# FanSCH.net
KiCad netlist of a schematic drawn in Altium Designer
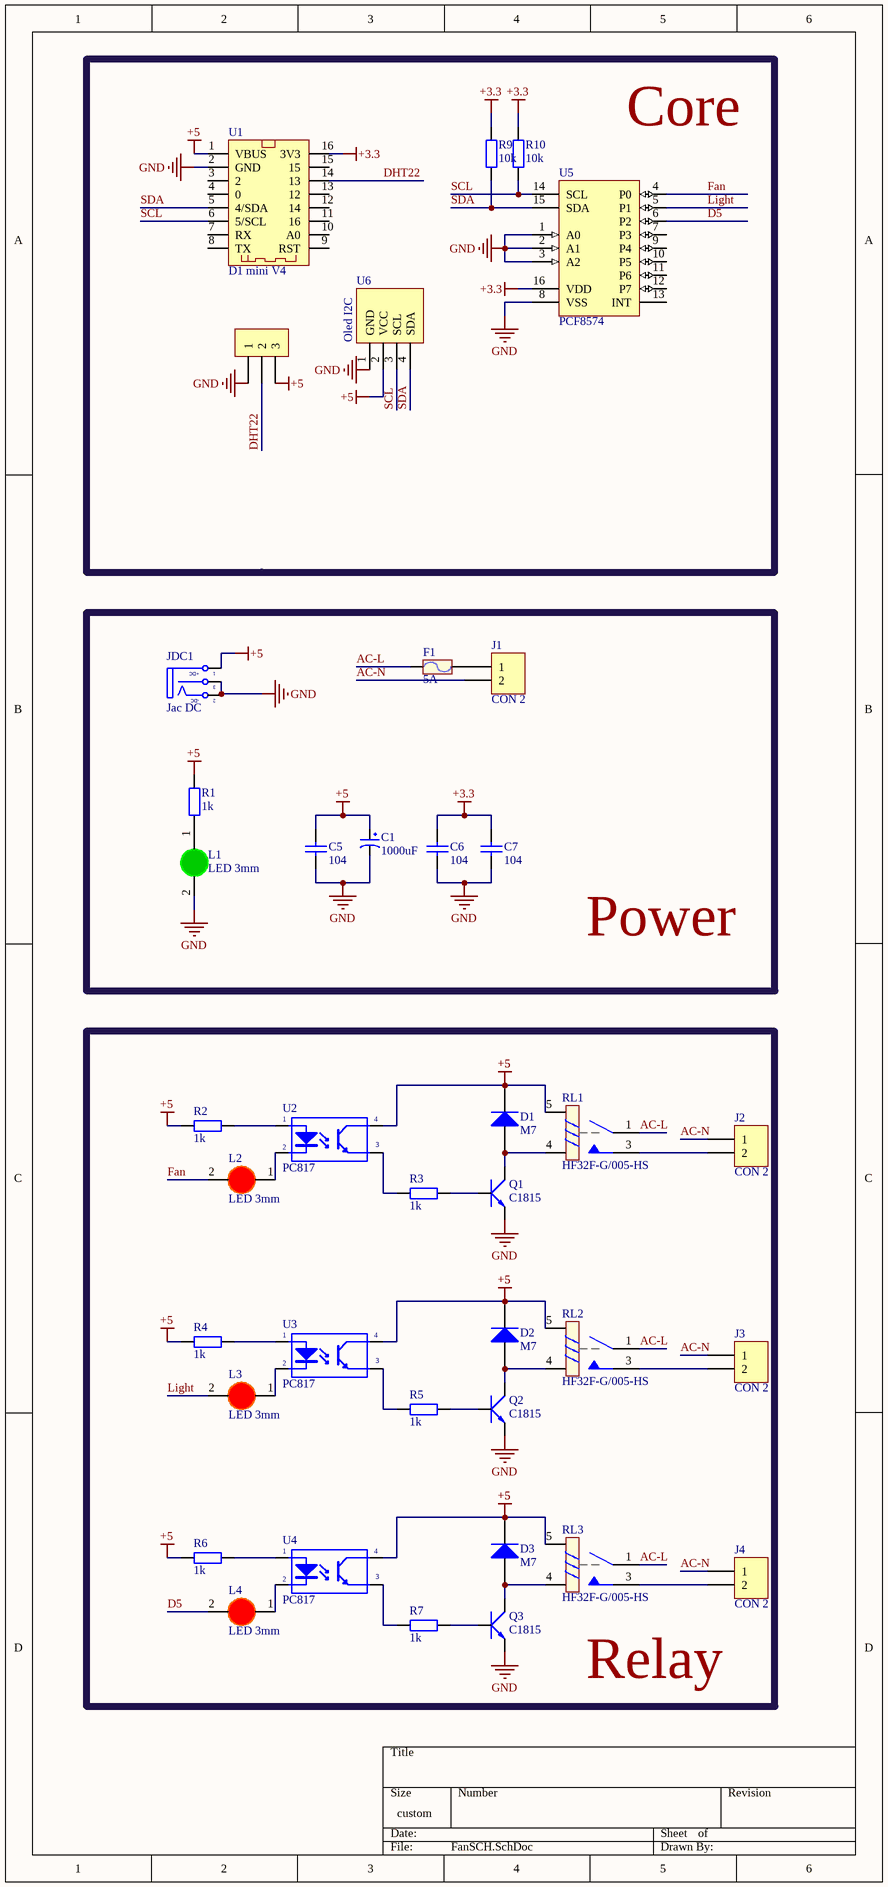
[diagram p0: FanSCH.SchDoc]

(export (version "E")
  (design (tool "Eeschema 10.0.6"))
  (components
    (comp (ref "C1")
      (value "1000uF")
      (footprint "tu hoa 8mm")
      (description "Cắm")
      (libsource (lib "Altium_Lib_by_KhueNguyenCreator") (part "Tu Hoa 1000uF 16V 8x20"))
    )
    (comp (ref "C5")
      (value "104")
      (footprint "tu 0603")
      (description "Dán")
      (libsource (lib "Altium_Lib_by_KhueNguyenCreator") (part "Tu 0603 104 50V 10%"))
    )
    (comp (ref "C6")
      (value "104")
      (footprint "tu 0603")
      (description "Dán")
      (libsource (lib "Altium_Lib_by_KhueNguyenCreator") (part "Tu 0603 104 50V 10%"))
    )
    (comp (ref "C7")
      (value "104")
      (footprint "tu 0603")
      (description "Dán")
      (libsource (lib "Altium_Lib_by_KhueNguyenCreator") (part "Tu 0603 104 50V 10%"))
    )
    (comp (ref "D1")
      (value "M7")
      (footprint "DIODE SMA")
      (description "Dán")
      (libsource (lib "Altium_Lib_by_KhueNguyenCreator") (part "Diode M7 ( 4007 )"))
    )
    (comp (ref "D2")
      (value "M7")
      (footprint "DIODE SMA")
      (description "Dán")
      (libsource (lib "Altium_Lib_by_KhueNguyenCreator") (part "Diode M7 ( 4007 )"))
    )
    (comp (ref "D3")
      (value "M7")
      (footprint "DIODE SMA")
      (description "Dán")
      (libsource (lib "Altium_Lib_by_KhueNguyenCreator") (part "Diode M7 ( 4007 )"))
    )
    (comp (ref "F1")
      (value "5A")
      (footprint "Fuse rectangular")
      (description "Fuse")
      (fields (field (name "DESIGNED BY") "VanDungEvn"))
      (libsource (lib "iuh-thuc-hanh") (part "Fuse"))
    )
    (comp (ref "H1")
      (value "Header 3P VH3.96 Duc Thang")
      (footprint "VH3.96M-3")
      (description "Cắm")
      (libsource (lib "Altium_Lib_by_KhueNguyenCreator") (part "Header 3P VH3.96 Duc Thang"))
    )
    (comp (ref "J1")
      (value "CON 2")
      (footprint "CON 2 2EDG5.08")
      (description "CON2 KF terminal")
      (libsource (lib "iuh-thuc-hanh") (part "CON 2 EDG5.08"))
    )
    (comp (ref "J2")
      (value "CON 2")
      (footprint "CON 2 2EDG5.08")
      (description "CON2 KF terminal")
      (libsource (lib "iuh-thuc-hanh") (part "CON 2 EDG5.08"))
    )
    (comp (ref "J3")
      (value "CON 2")
      (footprint "CON 2 2EDG5.08")
      (description "CON2 KF terminal")
      (libsource (lib "iuh-thuc-hanh") (part "CON 2 EDG5.08"))
    )
    (comp (ref "J4")
      (value "CON 2")
      (footprint "CON 2 2EDG5.08")
      (description "CON2 KF terminal")
      (libsource (lib "iuh-thuc-hanh") (part "CON 2 EDG5.08"))
    )
    (comp (ref "JDC1")
      (value "Jac DC")
      (footprint "DC0")
      (description "Jac DC input")
      (libsource (lib "LIBRARY1") (part "DCIN"))
    )
    (comp (ref "L1")
      (value "LED 3mm")
      (footprint "LED-3MM-GREEN")
      (description "Cắm")
      (libsource (lib "Altium_Lib_by_KhueNguyenCreator") (part "LED 3mm Xanh La"))
    )
    (comp (ref "L2")
      (value "LED 3mm")
      (footprint "LED-3MM-RED")
      (description "Cắm")
      (libsource (lib "Altium_Lib_by_KhueNguyenCreator") (part "LED 3mm Do"))
    )
    (comp (ref "L3")
      (value "LED 3mm")
      (footprint "LED-3MM-RED")
      (description "Cắm")
      (libsource (lib "Altium_Lib_by_KhueNguyenCreator") (part "LED 3mm Do"))
    )
    (comp (ref "L4")
      (value "LED 3mm")
      (footprint "LED-3MM-RED")
      (description "Cắm")
      (libsource (lib "Altium_Lib_by_KhueNguyenCreator") (part "LED 3mm Do"))
    )
    (comp (ref "Q1")
      (value "C1815")
      (footprint "TO92")
      (description "NPN transistor")
      (libsource (lib "Altium_Lib_by_KhueNguyenCreator") (part "Trans C1815 DIP"))
    )
    (comp (ref "Q2")
      (value "C1815")
      (footprint "TO92")
      (description "NPN transistor")
      (libsource (lib "Altium_Lib_by_KhueNguyenCreator") (part "Trans C1815 DIP"))
    )
    (comp (ref "Q3")
      (value "C1815")
      (footprint "TO92")
      (description "NPN transistor")
      (libsource (lib "Altium_Lib_by_KhueNguyenCreator") (part "Trans C1815 DIP"))
    )
    (comp (ref "R1")
      (value "1k")
      (footprint "tro smd 0603")
      (description "Dán")
      (libsource (lib "Altium_Lib_by_KhueNguyenCreator") (part "Tro 0603 1% 1k"))
    )
    (comp (ref "R2")
      (value "1k")
      (footprint "tro smd 0603")
      (description "Dán")
      (libsource (lib "Altium_Lib_by_KhueNguyenCreator") (part "Tro 0603 1% 1k"))
    )
    (comp (ref "R3")
      (value "1k")
      (footprint "tro smd 0603")
      (description "Dán")
      (libsource (lib "Altium_Lib_by_KhueNguyenCreator") (part "Tro 0603 1% 1k"))
    )
    (comp (ref "R4")
      (value "1k")
      (footprint "tro smd 0603")
      (description "Dán")
      (libsource (lib "Altium_Lib_by_KhueNguyenCreator") (part "Tro 0603 1% 1k"))
    )
    (comp (ref "R5")
      (value "1k")
      (footprint "tro smd 0603")
      (description "Dán")
      (libsource (lib "Altium_Lib_by_KhueNguyenCreator") (part "Tro 0603 1% 1k"))
    )
    (comp (ref "R6")
      (value "1k")
      (footprint "tro smd 0603")
      (description "Dán")
      (libsource (lib "Altium_Lib_by_KhueNguyenCreator") (part "Tro 0603 1% 1k"))
    )
    (comp (ref "R7")
      (value "1k")
      (footprint "tro smd 0603")
      (description "Dán")
      (libsource (lib "Altium_Lib_by_KhueNguyenCreator") (part "Tro 0603 1% 1k"))
    )
    (comp (ref "R9")
      (value "10k")
      (footprint "tro smd 0603")
      (description "Dán")
      (libsource (lib "Altium_Lib_by_KhueNguyenCreator") (part "Tro 0603 1% 10k"))
    )
    (comp (ref "R10")
      (value "10k")
      (footprint "tro smd 0603")
      (description "Dán")
      (libsource (lib "Altium_Lib_by_KhueNguyenCreator") (part "Tro 0603 1% 10k"))
    )
    (comp (ref "RL1")
      (value "HF32F-G/005-HS")
      (footprint "HF32F-G")
      (description "Relay hongfa 10A 4P HF32F-G/005-HS")
      (libsource (lib "iuh-thuc-hanh") (part "Relay HF 10A"))
    )
    (comp (ref "RL2")
      (value "HF32F-G/005-HS")
      (footprint "HF32F-G")
      (description "Relay hongfa 10A 4P HF32F-G/005-HS")
      (libsource (lib "iuh-thuc-hanh") (part "Relay HF 10A"))
    )
    (comp (ref "RL3")
      (value "HF32F-G/005-HS")
      (footprint "HF32F-G")
      (description "Relay hongfa 10A 4P HF32F-G/005-HS")
      (libsource (lib "iuh-thuc-hanh") (part "Relay HF 10A"))
    )
    (comp (ref "U1")
      (value "D1 mini V4")
      (footprint "WEMOS D1 MINI V4 USD")
      (description "ESP8266 D1")
      (libsource (lib "iuh-thuc-hanh") (part "Wemos D1 mini V4.0"))
    )
    (comp (ref "U2")
      (value "PC817")
      (footprint "DIP4")
      (description "Single Opto")
      (libsource (lib "LIBRARY1") (part "PC817"))
    )
    (comp (ref "U3")
      (value "PC817")
      (footprint "DIP4")
      (description "Single Opto")
      (libsource (lib "LIBRARY1") (part "PC817"))
    )
    (comp (ref "U4")
      (value "PC817")
      (footprint "DIP4")
      (description "Single Opto")
      (libsource (lib "LIBRARY1") (part "PC817"))
    )
    (comp (ref "U5") (value "PCF8574") (footprint "DIP16") (libsource (lib "iuh-thuc-hanh") (part "PCF8574")))
    (comp (ref "U6") (value "Oled I2C") (footprint "Oled") (libsource (lib "Nathzz") (part "Oled I2C")))
  )
  (nets
    (net (code "1") (name "+3.3") (class "Default")
      (node (ref "C6") (pin "2") (pinfunction "2_2") (pintype "passive"))
      (node (ref "C7") (pin "2") (pinfunction "2_2") (pintype "passive"))
      (node (ref "R10") (pin "2") (pinfunction "2_2") (pintype "passive"))
      (node (ref "R9") (pin "2") (pinfunction "2_2") (pintype "passive"))
      (node (ref "U1") (pin "16") (pinfunction "3V3_16") (pintype "passive"))
      (node (ref "U5") (pin "16") (pinfunction "VDD_16") (pintype "passive"))
    )
    (net (code "2") (name "+5") (class "Default")
      (node (ref "C1") (pin "1") (pinfunction "1_1") (pintype "passive"))
      (node (ref "C5") (pin "2") (pinfunction "2_2") (pintype "passive"))
      (node (ref "D1") (pin "2") (pinfunction "K_2") (pintype "passive"))
      (node (ref "D2") (pin "2") (pinfunction "K_2") (pintype "passive"))
      (node (ref "D3") (pin "2") (pinfunction "K_2") (pintype "passive"))
      (node (ref "H1") (pin "3") (pinfunction "3_3") (pintype "passive"))
      (node (ref "JDC1") (pin "1") (pinfunction "T_1") (pintype "passive"))
      (node (ref "R1") (pin "2") (pinfunction "2_2") (pintype "passive"))
      (node (ref "R2") (pin "1") (pinfunction "1_1") (pintype "passive"))
      (node (ref "R4") (pin "1") (pinfunction "1_1") (pintype "passive"))
      (node (ref "R6") (pin "1") (pinfunction "1_1") (pintype "passive"))
      (node (ref "RL1") (pin "5") (pinfunction "5_5") (pintype "passive"))
      (node (ref "RL2") (pin "5") (pinfunction "5_5") (pintype "passive"))
      (node (ref "RL3") (pin "5") (pinfunction "5_5") (pintype "passive"))
      (node (ref "U1") (pin "1") (pinfunction "VBUS_1") (pintype "passive"))
      (node (ref "U2") (pin "4") (pinfunction "C_4") (pintype "passive"))
      (node (ref "U3") (pin "4") (pinfunction "C_4") (pintype "passive"))
      (node (ref "U4") (pin "4") (pinfunction "C_4") (pintype "passive"))
      (node (ref "U6") (pin "2") (pinfunction "VCC_2") (pintype "passive"))
    )
    (net (code "3") (name "/AC-L") (class "Default")
      (node (ref "F1") (pin "1") (pinfunction "1_1") (pintype "passive"))
      (node (ref "RL1") (pin "1") (pinfunction "1_1") (pintype "passive"))
      (node (ref "RL2") (pin "1") (pinfunction "1_1") (pintype "passive"))
      (node (ref "RL3") (pin "1") (pinfunction "1_1") (pintype "passive"))
    )
    (net (code "4") (name "/AC-N") (class "Default")
      (node (ref "J1") (pin "2") (pinfunction "2_2") (pintype "passive"))
      (node (ref "J2") (pin "1") (pinfunction "1_1") (pintype "passive"))
      (node (ref "J3") (pin "1") (pinfunction "1_1") (pintype "passive"))
      (node (ref "J4") (pin "1") (pinfunction "1_1") (pintype "passive"))
    )
    (net (code "5") (name "/D5") (class "Default")
      (node (ref "L4") (pin "2") (pinfunction "K_2") (pintype "passive"))
      (node (ref "U5") (pin "6") (pinfunction "P2_6") (pintype "bidirectional"))
    )
    (net (code "6") (name "/DHT22") (class "Default")
      (node (ref "H1") (pin "2") (pinfunction "2_2") (pintype "passive"))
      (node (ref "U1") (pin "14") (pinfunction "13_14") (pintype "passive"))
    )
    (net (code "7") (name "/Fan") (class "Default")
      (node (ref "L2") (pin "2") (pinfunction "K_2") (pintype "passive"))
      (node (ref "U5") (pin "4") (pinfunction "P0_4") (pintype "bidirectional"))
    )
    (net (code "8") (name "/Light") (class "Default")
      (node (ref "L3") (pin "2") (pinfunction "K_2") (pintype "passive"))
      (node (ref "U5") (pin "5") (pinfunction "P1_5") (pintype "bidirectional"))
    )
    (net (code "9") (name "/SCL") (class "Default")
      (node (ref "R10") (pin "1") (pinfunction "1_1") (pintype "passive"))
      (node (ref "U1") (pin "6") (pinfunction "5/SCL_6") (pintype "passive"))
      (node (ref "U5") (pin "14") (pinfunction "SCL_14") (pintype "passive"))
      (node (ref "U6") (pin "3") (pinfunction "SCL_3") (pintype "passive"))
    )
    (net (code "10") (name "/SDA") (class "Default")
      (node (ref "R9") (pin "1") (pinfunction "1_1") (pintype "passive"))
      (node (ref "U1") (pin "5") (pinfunction "4/SDA_5") (pintype "passive"))
      (node (ref "U5") (pin "15") (pinfunction "SDA_15") (pintype "passive"))
      (node (ref "U6") (pin "4") (pinfunction "SDA_4") (pintype "passive"))
    )
    (net (code "11") (name "GND") (class "Default")
      (node (ref "C1") (pin "2") (pinfunction "2_2") (pintype "passive"))
      (node (ref "C5") (pin "1") (pinfunction "1_1") (pintype "passive"))
      (node (ref "C6") (pin "1") (pinfunction "1_1") (pintype "passive"))
      (node (ref "C7") (pin "1") (pinfunction "1_1") (pintype "passive"))
      (node (ref "H1") (pin "1") (pinfunction "1_1") (pintype "passive"))
      (node (ref "JDC1") (pin "2") (pinfunction "TN_2") (pintype "passive"))
      (node (ref "JDC1") (pin "3") (pinfunction "S_3") (pintype "power_in"))
      (node (ref "L1") (pin "2") (pinfunction "K_2") (pintype "passive"))
      (node (ref "Q1") (pin "1") (pinfunction "E_1") (pintype "passive"))
      (node (ref "Q2") (pin "1") (pinfunction "E_1") (pintype "passive"))
      (node (ref "Q3") (pin "1") (pinfunction "E_1") (pintype "passive"))
      (node (ref "U1") (pin "2") (pinfunction "GND_2") (pintype "passive"))
      (node (ref "U5") (pin "1") (pinfunction "A0_1") (pintype "input"))
      (node (ref "U5") (pin "2") (pinfunction "A1_2") (pintype "input"))
      (node (ref "U5") (pin "3") (pinfunction "A2_3") (pintype "input"))
      (node (ref "U5") (pin "8") (pinfunction "VSS_8") (pintype "passive"))
      (node (ref "U6") (pin "1") (pinfunction "GND_1") (pintype "passive"))
    )
    (net (code "12") (name "Net-(D1-A)") (class "Default")
      (node (ref "D1") (pin "1") (pinfunction "A_1") (pintype "passive"))
      (node (ref "Q1") (pin "2") (pinfunction "C_2") (pintype "passive"))
      (node (ref "RL1") (pin "4") (pinfunction "4_4") (pintype "passive"))
    )
    (net (code "13") (name "Net-(D2-A)") (class "Default")
      (node (ref "D2") (pin "1") (pinfunction "A_1") (pintype "passive"))
      (node (ref "Q2") (pin "2") (pinfunction "C_2") (pintype "passive"))
      (node (ref "RL2") (pin "4") (pinfunction "4_4") (pintype "passive"))
    )
    (net (code "14") (name "Net-(D3-A)") (class "Default")
      (node (ref "D3") (pin "1") (pinfunction "A_1") (pintype "passive"))
      (node (ref "Q3") (pin "2") (pinfunction "C_2") (pintype "passive"))
      (node (ref "RL3") (pin "4") (pinfunction "4_4") (pintype "passive"))
    )
    (net (code "15") (name "Net-(F1-Pad2)") (class "Default")
      (node (ref "F1") (pin "2") (pinfunction "2_2") (pintype "passive"))
      (node (ref "J1") (pin "1") (pinfunction "1_1") (pintype "passive"))
    )
    (net (code "16") (name "Net-(J2-Pad2)") (class "Default")
      (node (ref "J2") (pin "2") (pinfunction "2_2") (pintype "passive"))
      (node (ref "RL1") (pin "3") (pinfunction "3_3") (pintype "passive"))
    )
    (net (code "17") (name "Net-(J3-Pad2)") (class "Default")
      (node (ref "J3") (pin "2") (pinfunction "2_2") (pintype "passive"))
      (node (ref "RL2") (pin "3") (pinfunction "3_3") (pintype "passive"))
    )
    (net (code "18") (name "Net-(J4-Pad2)") (class "Default")
      (node (ref "J4") (pin "2") (pinfunction "2_2") (pintype "passive"))
      (node (ref "RL3") (pin "3") (pinfunction "3_3") (pintype "passive"))
    )
    (net (code "19") (name "Net-(L1-A)") (class "Default")
      (node (ref "L1") (pin "1") (pinfunction "A_1") (pintype "passive"))
      (node (ref "R1") (pin "1") (pinfunction "1_1") (pintype "passive"))
    )
    (net (code "20") (name "Net-(L2-A)") (class "Default")
      (node (ref "L2") (pin "1") (pinfunction "A_1") (pintype "passive"))
      (node (ref "U2") (pin "2") (pinfunction "K_2") (pintype "passive"))
    )
    (net (code "21") (name "Net-(L3-A)") (class "Default")
      (node (ref "L3") (pin "1") (pinfunction "A_1") (pintype "passive"))
      (node (ref "U3") (pin "2") (pinfunction "K_2") (pintype "passive"))
    )
    (net (code "22") (name "Net-(L4-A)") (class "Default")
      (node (ref "L4") (pin "1") (pinfunction "A_1") (pintype "passive"))
      (node (ref "U4") (pin "2") (pinfunction "K_2") (pintype "passive"))
    )
    (net (code "23") (name "Net-(Q1-B)") (class "Default")
      (node (ref "Q1") (pin "3") (pinfunction "B_3") (pintype "passive"))
      (node (ref "R3") (pin "2") (pinfunction "2_2") (pintype "passive"))
    )
    (net (code "24") (name "Net-(Q2-B)") (class "Default")
      (node (ref "Q2") (pin "3") (pinfunction "B_3") (pintype "passive"))
      (node (ref "R5") (pin "2") (pinfunction "2_2") (pintype "passive"))
    )
    (net (code "25") (name "Net-(Q3-B)") (class "Default")
      (node (ref "Q3") (pin "3") (pinfunction "B_3") (pintype "passive"))
      (node (ref "R7") (pin "2") (pinfunction "2_2") (pintype "passive"))
    )
    (net (code "26") (name "Net-(U2-A)") (class "Default")
      (node (ref "R2") (pin "2") (pinfunction "2_2") (pintype "passive"))
      (node (ref "U2") (pin "1") (pinfunction "A_1") (pintype "passive"))
    )
    (net (code "27") (name "Net-(U2-E)") (class "Default")
      (node (ref "R3") (pin "1") (pinfunction "1_1") (pintype "passive"))
      (node (ref "U2") (pin "3") (pinfunction "E_3") (pintype "passive"))
    )
    (net (code "28") (name "Net-(U3-A)") (class "Default")
      (node (ref "R4") (pin "2") (pinfunction "2_2") (pintype "passive"))
      (node (ref "U3") (pin "1") (pinfunction "A_1") (pintype "passive"))
    )
    (net (code "29") (name "Net-(U3-E)") (class "Default")
      (node (ref "R5") (pin "1") (pinfunction "1_1") (pintype "passive"))
      (node (ref "U3") (pin "3") (pinfunction "E_3") (pintype "passive"))
    )
    (net (code "30") (name "Net-(U4-A)") (class "Default")
      (node (ref "R6") (pin "2") (pinfunction "2_2") (pintype "passive"))
      (node (ref "U4") (pin "1") (pinfunction "A_1") (pintype "passive"))
    )
    (net (code "31") (name "Net-(U4-E)") (class "Default")
      (node (ref "R7") (pin "1") (pinfunction "1_1") (pintype "passive"))
      (node (ref "U4") (pin "3") (pinfunction "E_3") (pintype "passive"))
    )
    (net (code "32") (name "unconnected-(U1-0-Pad4)") (class "Default")
      (node (ref "U1") (pin "4") (pinfunction "0_4") (pintype "passive"))
    )
    (net (code "33") (name "unconnected-(U1-2-Pad3)") (class "Default")
      (node (ref "U1") (pin "3") (pinfunction "2_3") (pintype "passive"))
    )
    (net (code "34") (name "unconnected-(U1-12-Pad13)") (class "Default")
      (node (ref "U1") (pin "13") (pinfunction "12_13") (pintype "passive"))
    )
    (net (code "35") (name "unconnected-(U1-14-Pad12)") (class "Default")
      (node (ref "U1") (pin "12") (pinfunction "14_12") (pintype "passive"))
    )
    (net (code "36") (name "unconnected-(U1-16-Pad11)") (class "Default")
      (node (ref "U1") (pin "11") (pinfunction "16_11") (pintype "passive"))
    )
    (net (code "37") (name "unconnected-(U1-A0-Pad10)") (class "Default")
      (node (ref "U1") (pin "10") (pinfunction "A0_10") (pintype "passive"))
    )
    (net (code "38") (name "unconnected-(U1-Pad15)") (class "Default")
      (node (ref "U1") (pin "15") (pinfunction "15_15") (pintype "passive"))
    )
    (net (code "39") (name "unconnected-(U1-RST-Pad9)") (class "Default")
      (node (ref "U1") (pin "9") (pinfunction "RST_9") (pintype "passive"))
    )
    (net (code "40") (name "unconnected-(U1-RX-Pad7)") (class "Default")
      (node (ref "U1") (pin "7") (pinfunction "RX_7") (pintype "passive"))
    )
    (net (code "41") (name "unconnected-(U1-TX-Pad8)") (class "Default")
      (node (ref "U1") (pin "8") (pinfunction "TX_8") (pintype "passive"))
    )
    (net (code "42") (name "unconnected-(U5-INT-Pad13)") (class "Default")
      (node (ref "U5") (pin "13") (pinfunction "INT_13") (pintype "passive"))
    )
    (net (code "43") (name "unconnected-(U5-P3-Pad7)") (class "Default")
      (node (ref "U5") (pin "7") (pinfunction "P3_7") (pintype "bidirectional"))
    )
    (net (code "44") (name "unconnected-(U5-P4-Pad9)") (class "Default")
      (node (ref "U5") (pin "9") (pinfunction "P4_9") (pintype "bidirectional"))
    )
    (net (code "45") (name "unconnected-(U5-P5-Pad10)") (class "Default")
      (node (ref "U5") (pin "10") (pinfunction "P5_10") (pintype "bidirectional"))
    )
    (net (code "46") (name "unconnected-(U5-P6-Pad11)") (class "Default")
      (node (ref "U5") (pin "11") (pinfunction "P6_11") (pintype "bidirectional"))
    )
    (net (code "47") (name "unconnected-(U5-P7-Pad12)") (class "Default")
      (node (ref "U5") (pin "12") (pinfunction "P7_12") (pintype "bidirectional"))
    )
  )
)
